# Sheet1.net
KiCad netlist of a schematic drawn in Altium Designer
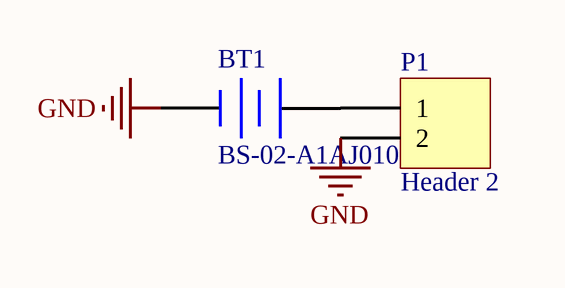
[diagram p0: Sheet1.SchDoc]

(export (version "E")
  (design (tool "Eeschema 10.0.6"))
  (components
    (comp (ref "BT1")
      (value "BS-02-A1AJ010")
      (footprint "BS-02-A1AJ010")
      (description "Multicell Battery")
      (fields (field (name "PUBLISHER") "Altium Limited"))
      (libsource (lib "Miscellaneous Devices") (part "Battery"))
    )
    (comp (ref "P1")
      (value "Header 2")
      (footprint "2x2.0mm_smt")
      (description "Header, 2-Pin")
      (fields (field (name "PUBLISHER") "Altium Limited"))
      (libsource (lib "Miscellaneous Connectors") (part "Header 2"))
    )
  )
  (nets
    (net (code "1") (name "GND") (class "Default")
      (node (ref "BT1") (pin "2") (pinfunction "-_2") (pintype "passive"))
      (node (ref "P1") (pin "2") (pinfunction "2_2") (pintype "passive"))
    )
    (net (code "2") (name "Net-(BT1-+)") (class "Default")
      (node (ref "BT1") (pin "1") (pinfunction "+_1") (pintype "passive"))
      (node (ref "P1") (pin "1") (pinfunction "1_1") (pintype "passive"))
    )
  )
)
